# Sheet1.net
KiCad netlist of a schematic drawn in Altium Designer
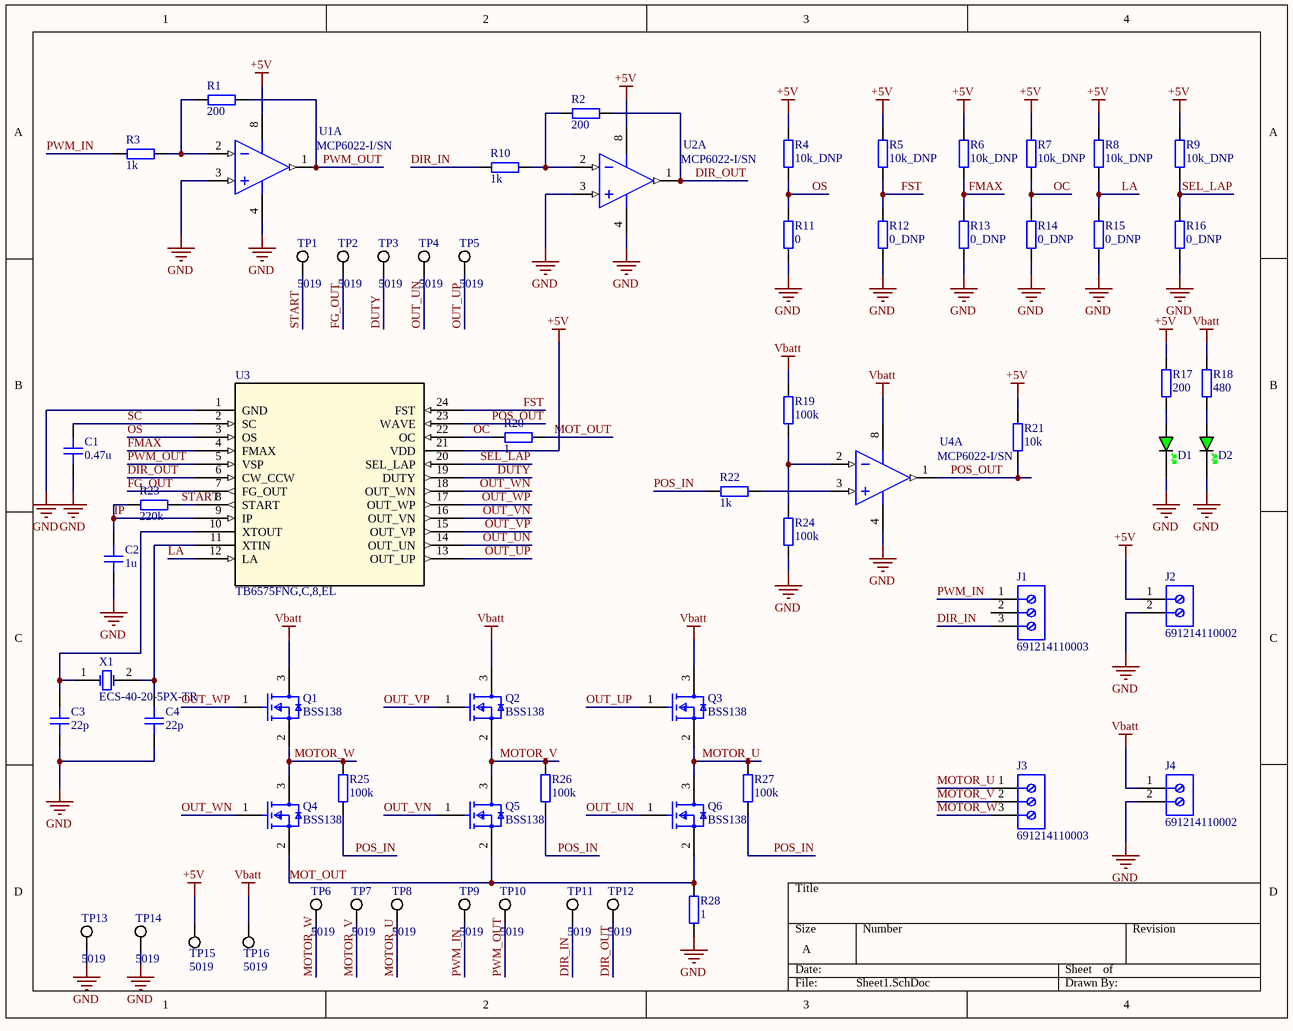
[diagram p0: Sheet1.SchDoc]

(export (version "E")
  (design (tool "Eeschema 10.0.6"))
  (components
    (comp (ref "C1")
      (value "0.47u")
      (footprint "CAP_0805")
      (description "Capacitor SMD 0805")
      (libsource (lib "Schematic-Lib-PhilsLab") (part "CAP_0805"))
    )
    (comp (ref "C2")
      (value "1u")
      (footprint "CAP_0805")
      (description "Capacitor SMD 0805")
      (libsource (lib "Schematic-Lib-PhilsLab") (part "CAP_0805"))
    )
    (comp (ref "C3")
      (value "22p")
      (footprint "CAP_0805")
      (description "Capacitor SMD 0805")
      (libsource (lib "Schematic-Lib-PhilsLab") (part "CAP_0805"))
    )
    (comp (ref "C4")
      (value "22p")
      (footprint "CAP_0805")
      (description "Capacitor SMD 0805")
      (libsource (lib "Schematic-Lib-PhilsLab") (part "CAP_0805"))
    )
    (comp (ref "D1")
      (value "GREEN")
      (footprint "LED_0805_GREEN")
      (description "LED 0805 GREEN SMD")
      (libsource (lib "Schematic-Lib-PhilsLab") (part "LED_0805_GREEN"))
    )
    (comp (ref "D2")
      (value "GREEN")
      (footprint "LED_0805_GREEN")
      (description "LED 0805 GREEN SMD")
      (libsource (lib "Schematic-Lib-PhilsLab") (part "LED_0805_GREEN"))
    )
    (comp (ref "J1")
      (value "691214110003")
      (footprint "691214110003")
      (fields (field (name "VOLTAGE") "300V"))
      (libsource (lib "Altium Content Vault") (part "TBL - 1R - 03P - Screw"))
    )
    (comp (ref "J2")
      (value "691214110002")
      (footprint "691214110002")
      (fields (field (name "VOLTAGE") "300V"))
      (libsource (lib "Altium Content Vault") (part "TBL - 1R - 02P - Screw"))
    )
    (comp (ref "J3")
      (value "691214110003")
      (footprint "691214110003")
      (fields (field (name "VOLTAGE") "300V"))
      (libsource (lib "Altium Content Vault") (part "TBL - 1R - 03P - Screw"))
    )
    (comp (ref "J4")
      (value "691214110002")
      (footprint "691214110002")
      (fields (field (name "VOLTAGE") "300V"))
      (libsource (lib "Altium Content Vault") (part "TBL - 1R - 02P - Screw"))
    )
    (comp (ref "Q1")
      (value "BSS138")
      (footprint "FP-318-08-IPC_B")
      (description "MOSFET N-CH 50V 220MA SOT-23")
      (libsource (lib "Altium Content Vault") (part "3b9c635fedb024a5347a57b145af9cc"))
    )
    (comp (ref "Q2")
      (value "BSS138")
      (footprint "FP-318-08-IPC_B")
      (description "MOSFET N-CH 50V 220MA SOT-23")
      (libsource (lib "Altium Content Vault") (part "3b9c635fedb024a5347a57b145af9cc"))
    )
    (comp (ref "Q3")
      (value "BSS138")
      (footprint "FP-318-08-IPC_B")
      (description "MOSFET N-CH 50V 220MA SOT-23")
      (libsource (lib "Altium Content Vault") (part "3b9c635fedb024a5347a57b145af9cc"))
    )
    (comp (ref "Q4")
      (value "BSS138")
      (footprint "FP-318-08-IPC_B")
      (description "MOSFET N-CH 50V 220MA SOT-23")
      (libsource (lib "Altium Content Vault") (part "3b9c635fedb024a5347a57b145af9cc"))
    )
    (comp (ref "Q5")
      (value "BSS138")
      (footprint "FP-318-08-IPC_B")
      (description "MOSFET N-CH 50V 220MA SOT-23")
      (libsource (lib "Altium Content Vault") (part "3b9c635fedb024a5347a57b145af9cc"))
    )
    (comp (ref "Q6")
      (value "BSS138")
      (footprint "FP-318-08-IPC_B")
      (description "MOSFET N-CH 50V 220MA SOT-23")
      (libsource (lib "Altium Content Vault") (part "3b9c635fedb024a5347a57b145af9cc"))
    )
    (comp (ref "R1")
      (value "200")
      (footprint "RES_0805")
      (description "Resistor SMD 0805")
      (libsource (lib "Schematic-Lib-PhilsLab") (part "RES_0805"))
    )
    (comp (ref "R2")
      (value "200")
      (footprint "RES_0805")
      (description "Resistor SMD 0805")
      (libsource (lib "Schematic-Lib-PhilsLab") (part "RES_0805"))
    )
    (comp (ref "R3")
      (value "1k")
      (footprint "RES_0805")
      (description "Resistor SMD 0805")
      (libsource (lib "Schematic-Lib-PhilsLab") (part "RES_0805"))
    )
    (comp (ref "R4")
      (value "10k_DNP")
      (footprint "RES_0805")
      (description "Resistor SMD 0805")
      (libsource (lib "Schematic-Lib-PhilsLab") (part "RES_0805"))
    )
    (comp (ref "R5")
      (value "10k_DNP")
      (footprint "RES_0805")
      (description "Resistor SMD 0805")
      (libsource (lib "Schematic-Lib-PhilsLab") (part "RES_0805"))
    )
    (comp (ref "R6")
      (value "10k_DNP")
      (footprint "RES_0805")
      (description "Resistor SMD 0805")
      (libsource (lib "Schematic-Lib-PhilsLab") (part "RES_0805"))
    )
    (comp (ref "R7")
      (value "10k_DNP")
      (footprint "RES_0805")
      (description "Resistor SMD 0805")
      (libsource (lib "Schematic-Lib-PhilsLab") (part "RES_0805"))
    )
    (comp (ref "R8")
      (value "10k_DNP")
      (footprint "RES_0805")
      (description "Resistor SMD 0805")
      (libsource (lib "Schematic-Lib-PhilsLab") (part "RES_0805"))
    )
    (comp (ref "R9")
      (value "10k_DNP")
      (footprint "RES_0805")
      (description "Resistor SMD 0805")
      (libsource (lib "Schematic-Lib-PhilsLab") (part "RES_0805"))
    )
    (comp (ref "R10")
      (value "1k")
      (footprint "RES_0805")
      (description "Resistor SMD 0805")
      (libsource (lib "Schematic-Lib-PhilsLab") (part "RES_0805"))
    )
    (comp (ref "R11")
      (value "0")
      (footprint "RES_0805")
      (description "Resistor SMD 0805")
      (libsource (lib "Schematic-Lib-PhilsLab") (part "RES_0805"))
    )
    (comp (ref "R12")
      (value "0_DNP")
      (footprint "RES_0805")
      (description "Resistor SMD 0805")
      (libsource (lib "Schematic-Lib-PhilsLab") (part "RES_0805"))
    )
    (comp (ref "R13")
      (value "0_DNP")
      (footprint "RES_0805")
      (description "Resistor SMD 0805")
      (libsource (lib "Schematic-Lib-PhilsLab") (part "RES_0805"))
    )
    (comp (ref "R14")
      (value "0_DNP")
      (footprint "RES_0805")
      (description "Resistor SMD 0805")
      (libsource (lib "Schematic-Lib-PhilsLab") (part "RES_0805"))
    )
    (comp (ref "R15")
      (value "0_DNP")
      (footprint "RES_0805")
      (description "Resistor SMD 0805")
      (libsource (lib "Schematic-Lib-PhilsLab") (part "RES_0805"))
    )
    (comp (ref "R16")
      (value "0_DNP")
      (footprint "RES_0805")
      (description "Resistor SMD 0805")
      (libsource (lib "Schematic-Lib-PhilsLab") (part "RES_0805"))
    )
    (comp (ref "R17")
      (value "200")
      (footprint "RES_0805")
      (description "Resistor SMD 0805")
      (libsource (lib "Schematic-Lib-PhilsLab") (part "RES_0805"))
    )
    (comp (ref "R18")
      (value "480")
      (footprint "RES_0805")
      (description "Resistor SMD 0805")
      (libsource (lib "Schematic-Lib-PhilsLab") (part "RES_0805"))
    )
    (comp (ref "R19")
      (value "100k")
      (footprint "RES_0805")
      (description "Resistor SMD 0805")
      (libsource (lib "Schematic-Lib-PhilsLab") (part "RES_0805"))
    )
    (comp (ref "R20")
      (value "1")
      (footprint "RES_0805")
      (description "Resistor SMD 0805")
      (libsource (lib "Schematic-Lib-PhilsLab") (part "RES_0805"))
    )
    (comp (ref "R21")
      (value "10k")
      (footprint "RES_0805")
      (description "Resistor SMD 0805")
      (libsource (lib "Schematic-Lib-PhilsLab") (part "RES_0805"))
    )
    (comp (ref "R22")
      (value "1k")
      (footprint "RES_0805")
      (description "Resistor SMD 0805")
      (libsource (lib "Schematic-Lib-PhilsLab") (part "RES_0805"))
    )
    (comp (ref "R23")
      (value "220k")
      (footprint "RES_0805")
      (description "Resistor SMD 0805")
      (libsource (lib "Schematic-Lib-PhilsLab") (part "RES_0805"))
    )
    (comp (ref "R24")
      (value "100k")
      (footprint "RES_0805")
      (description "Resistor SMD 0805")
      (libsource (lib "Schematic-Lib-PhilsLab") (part "RES_0805"))
    )
    (comp (ref "R25")
      (value "100k")
      (footprint "RES_0805")
      (description "Resistor SMD 0805")
      (libsource (lib "Schematic-Lib-PhilsLab") (part "RES_0805"))
    )
    (comp (ref "R26")
      (value "100k")
      (footprint "RES_0805")
      (description "Resistor SMD 0805")
      (libsource (lib "Schematic-Lib-PhilsLab") (part "RES_0805"))
    )
    (comp (ref "R27")
      (value "100k")
      (footprint "RES_0805")
      (description "Resistor SMD 0805")
      (libsource (lib "Schematic-Lib-PhilsLab") (part "RES_0805"))
    )
    (comp (ref "R28")
      (value "1")
      (footprint "RES_0805")
      (description "Resistor SMD 0805")
      (libsource (lib "Schematic-Lib-PhilsLab") (part "RES_0805"))
    )
    (comp (ref "TP1")
      (value "5019")
      (footprint "KSTN-5019_V")
      (description "Test Point, 1 Position SMD, RoHS, Tape and Reel")
      (libsource (lib "Altium Content Vault") (part "TESTPOINT_WHITE"))
    )
    (comp (ref "TP2")
      (value "5019")
      (footprint "KSTN-5019_V")
      (description "Test Point, 1 Position SMD, RoHS, Tape and Reel")
      (libsource (lib "Altium Content Vault") (part "TESTPOINT_WHITE"))
    )
    (comp (ref "TP3")
      (value "5019")
      (footprint "KSTN-5019_V")
      (description "Test Point, 1 Position SMD, RoHS, Tape and Reel")
      (libsource (lib "Altium Content Vault") (part "TESTPOINT_WHITE"))
    )
    (comp (ref "TP4")
      (value "5019")
      (footprint "KSTN-5019_V")
      (description "Test Point, 1 Position SMD, RoHS, Tape and Reel")
      (libsource (lib "Altium Content Vault") (part "TESTPOINT_WHITE"))
    )
    (comp (ref "TP5")
      (value "5019")
      (footprint "KSTN-5019_V")
      (description "Test Point, 1 Position SMD, RoHS, Tape and Reel")
      (libsource (lib "Altium Content Vault") (part "TESTPOINT_WHITE"))
    )
    (comp (ref "TP6")
      (value "5019")
      (footprint "KSTN-5019_V")
      (description "Test Point, 1 Position SMD, RoHS, Tape and Reel")
      (libsource (lib "Altium Content Vault") (part "TESTPOINT_WHITE"))
    )
    (comp (ref "TP7")
      (value "5019")
      (footprint "KSTN-5019_V")
      (description "Test Point, 1 Position SMD, RoHS, Tape and Reel")
      (libsource (lib "Altium Content Vault") (part "TESTPOINT_WHITE"))
    )
    (comp (ref "TP8")
      (value "5019")
      (footprint "KSTN-5019_V")
      (description "Test Point, 1 Position SMD, RoHS, Tape and Reel")
      (libsource (lib "Altium Content Vault") (part "TESTPOINT_WHITE"))
    )
    (comp (ref "TP9")
      (value "5019")
      (footprint "KSTN-5019_V")
      (description "Test Point, 1 Position SMD, RoHS, Tape and Reel")
      (libsource (lib "Altium Content Vault") (part "TESTPOINT_WHITE"))
    )
    (comp (ref "TP10")
      (value "5019")
      (footprint "KSTN-5019_V")
      (description "Test Point, 1 Position SMD, RoHS, Tape and Reel")
      (libsource (lib "Altium Content Vault") (part "TESTPOINT_WHITE"))
    )
    (comp (ref "TP11")
      (value "5019")
      (footprint "KSTN-5019_V")
      (description "Test Point, 1 Position SMD, RoHS, Tape and Reel")
      (libsource (lib "Altium Content Vault") (part "TESTPOINT_WHITE"))
    )
    (comp (ref "TP12")
      (value "5019")
      (footprint "KSTN-5019_V")
      (description "Test Point, 1 Position SMD, RoHS, Tape and Reel")
      (libsource (lib "Altium Content Vault") (part "TESTPOINT_WHITE"))
    )
    (comp (ref "TP13")
      (value "5019")
      (footprint "KSTN-5019_V")
      (description "Test Point, 1 Position SMD, RoHS, Tape and Reel")
      (libsource (lib "Altium Content Vault") (part "TESTPOINT_WHITE"))
    )
    (comp (ref "TP14")
      (value "5019")
      (footprint "KSTN-5019_V")
      (description "Test Point, 1 Position SMD, RoHS, Tape and Reel")
      (libsource (lib "Altium Content Vault") (part "TESTPOINT_WHITE"))
    )
    (comp (ref "TP15")
      (value "5019")
      (footprint "KSTN-5019_V")
      (description "Test Point, 1 Position SMD, RoHS, Tape and Reel")
      (libsource (lib "Altium Content Vault") (part "TESTPOINT_WHITE"))
    )
    (comp (ref "TP16")
      (value "5019")
      (footprint "KSTN-5019_V")
      (description "Test Point, 1 Position SMD, RoHS, Tape and Reel")
      (libsource (lib "Altium Content Vault") (part "TESTPOINT_WHITE"))
    )
    (comp (ref "U1")
      (value "MCP6022-I/SN")
      (footprint "SOIC-SN8_N")
      (description "None")
      (libsource (lib "Altium Content Vault") (part "AMP-OPA-MCP6022-IL8"))
    )
    (comp (ref "U2")
      (value "MCP6022-I/SN")
      (footprint "SOIC-SN8_N")
      (description "None")
      (libsource (lib "Altium Content Vault") (part "AMP-OPA-MCP6022-IL8"))
    )
    (comp (ref "U3")
      (value "TB6575FNG,C,8,EL")
      (footprint "SSOP24-P-300-0p65A_TOS")
      (description "No Description Available")
      (libsource (lib "TB6575FNG,C,8,EL") (part "TB6575FNG,C,8,EL"))
    )
    (comp (ref "U4")
      (value "MCP6022-I/SN")
      (footprint "SOIC-SN8_N")
      (description "None")
      (libsource (lib "Altium Content Vault") (part "AMP-OPA-MCP6022-IL8"))
    )
    (comp (ref "X1")
      (value "ECS-40-20-5PX-TR")
      (footprint "ABRA-ABLS-14.7456MHZ-B2-T_V")
      (description "Low Profile Crystal, 8.0 MHz, +/- 30 ppm, -20 to 70 degC, 2-Pin SMD, RoHS, Tape and Reel")
      (fields (field (name "MANUFACTURER") "ABRACON") (field (name "TOLERANCE") "30PPM"))
      (libsource (lib "Altium Content Vault") (part "XTAL_1-2-2"))
    )
  )
  (nets
    (net (code "1") (name "+5V") (class "Default")
      (node (ref "J2") (pin "1") (pinfunction "1_1") (pintype "passive"))
      (node (ref "R17") (pin "2") (pinfunction "2_2") (pintype "passive"))
      (node (ref "R21") (pin "2") (pinfunction "2_2") (pintype "passive"))
      (node (ref "R4") (pin "2") (pinfunction "2_2") (pintype "passive"))
      (node (ref "R5") (pin "2") (pinfunction "2_2") (pintype "passive"))
      (node (ref "R6") (pin "2") (pinfunction "2_2") (pintype "passive"))
      (node (ref "R7") (pin "2") (pinfunction "2_2") (pintype "passive"))
      (node (ref "R8") (pin "2") (pinfunction "2_2") (pintype "passive"))
      (node (ref "R9") (pin "2") (pinfunction "2_2") (pintype "passive"))
      (node (ref "TP15") (pin "1") (pinfunction "1_1") (pintype "passive"))
      (node (ref "U1") (pin "8") (pinfunction "VDD_8") (pintype "power_in"))
      (node (ref "U2") (pin "8") (pinfunction "VDD_8") (pintype "power_in"))
      (node (ref "U3") (pin "21") (pinfunction "VDD_21") (pintype "power_in"))
    )
    (net (code "2") (name "/DIR_IN") (class "Default")
      (node (ref "J1") (pin "3") (pinfunction "3_3") (pintype "passive"))
      (node (ref "R10") (pin "1") (pinfunction "1_1") (pintype "passive"))
      (node (ref "TP11") (pin "1") (pinfunction "1_1") (pintype "passive"))
    )
    (net (code "3") (name "/DIR_OUT") (class "Default")
      (node (ref "R2") (pin "2") (pinfunction "2_2") (pintype "passive"))
      (node (ref "TP12") (pin "1") (pinfunction "1_1") (pintype "passive"))
      (node (ref "U2") (pin "1") (pinfunction "VOUTA_1") (pintype "output"))
      (node (ref "U3") (pin "6") (pinfunction "CW_CCW_6") (pintype "input"))
    )
    (net (code "4") (name "/DUTY") (class "Default")
      (node (ref "TP3") (pin "1") (pinfunction "1_1") (pintype "passive"))
      (node (ref "U3") (pin "19") (pinfunction "DUTY_19") (pintype "output"))
    )
    (net (code "5") (name "/FG_OUT") (class "Default")
      (node (ref "TP2") (pin "1") (pinfunction "1_1") (pintype "passive"))
      (node (ref "U3") (pin "7") (pinfunction "FG_OUT_7") (pintype "output"))
    )
    (net (code "6") (name "/FMAX") (class "Default")
      (node (ref "R13") (pin "2") (pinfunction "2_2") (pintype "passive"))
      (node (ref "R6") (pin "1") (pinfunction "1_1") (pintype "passive"))
      (node (ref "U3") (pin "4") (pinfunction "FMAX_4") (pintype "input"))
    )
    (net (code "7") (name "/FST") (class "Default")
      (node (ref "R12") (pin "2") (pinfunction "2_2") (pintype "passive"))
      (node (ref "R5") (pin "1") (pinfunction "1_1") (pintype "passive"))
      (node (ref "U3") (pin "24") (pinfunction "FST_24") (pintype "input"))
    )
    (net (code "8") (name "/IP") (class "Default")
      (node (ref "C2") (pin "2") (pinfunction "2_2") (pintype "passive"))
      (node (ref "R23") (pin "2") (pinfunction "2_2") (pintype "passive"))
      (node (ref "U3") (pin "9") (pinfunction "IP_9") (pintype "input"))
    )
    (net (code "9") (name "/LA") (class "Default")
      (node (ref "R15") (pin "2") (pinfunction "2_2") (pintype "passive"))
      (node (ref "R8") (pin "1") (pinfunction "1_1") (pintype "passive"))
      (node (ref "U3") (pin "12") (pinfunction "LA_12") (pintype "input"))
    )
    (net (code "10") (name "/MOTOR_U") (class "Default")
      (node (ref "J3") (pin "1") (pinfunction "1_1") (pintype "passive"))
      (node (ref "Q3") (pin "2") (pinfunction "S_2") (pintype "passive"))
      (node (ref "Q6") (pin "3") (pinfunction "D_3") (pintype "passive"))
      (node (ref "R27") (pin "2") (pinfunction "2_2") (pintype "passive"))
      (node (ref "TP8") (pin "1") (pinfunction "1_1") (pintype "passive"))
    )
    (net (code "11") (name "/MOTOR_V") (class "Default")
      (node (ref "J3") (pin "2") (pinfunction "2_2") (pintype "passive"))
      (node (ref "Q2") (pin "2") (pinfunction "S_2") (pintype "passive"))
      (node (ref "Q5") (pin "3") (pinfunction "D_3") (pintype "passive"))
      (node (ref "R26") (pin "2") (pinfunction "2_2") (pintype "passive"))
      (node (ref "TP7") (pin "1") (pinfunction "1_1") (pintype "passive"))
    )
    (net (code "12") (name "/MOTOR_W") (class "Default")
      (node (ref "J3") (pin "3") (pinfunction "3_3") (pintype "passive"))
      (node (ref "Q1") (pin "2") (pinfunction "S_2") (pintype "passive"))
      (node (ref "Q4") (pin "3") (pinfunction "D_3") (pintype "passive"))
      (node (ref "R25") (pin "2") (pinfunction "2_2") (pintype "passive"))
      (node (ref "TP6") (pin "1") (pinfunction "1_1") (pintype "passive"))
    )
    (net (code "13") (name "/MOT_OUT") (class "Default")
      (node (ref "Q4") (pin "2") (pinfunction "S_2") (pintype "passive"))
      (node (ref "Q5") (pin "2") (pinfunction "S_2") (pintype "passive"))
      (node (ref "Q6") (pin "2") (pinfunction "S_2") (pintype "passive"))
      (node (ref "R20") (pin "1") (pinfunction "1_1") (pintype "passive"))
      (node (ref "R28") (pin "2") (pinfunction "2_2") (pintype "passive"))
    )
    (net (code "14") (name "/OC") (class "Default")
      (node (ref "R14") (pin "2") (pinfunction "2_2") (pintype "passive"))
      (node (ref "R20") (pin "2") (pinfunction "2_2") (pintype "passive"))
      (node (ref "R7") (pin "1") (pinfunction "1_1") (pintype "passive"))
      (node (ref "U3") (pin "22") (pinfunction "OC_22") (pintype "input"))
    )
    (net (code "15") (name "/OS") (class "Default")
      (node (ref "R11") (pin "2") (pinfunction "2_2") (pintype "passive"))
      (node (ref "R4") (pin "1") (pinfunction "1_1") (pintype "passive"))
      (node (ref "U3") (pin "3") (pinfunction "OS_3") (pintype "input"))
    )
    (net (code "16") (name "/OUT_UN") (class "Default")
      (node (ref "Q6") (pin "1") (pinfunction "G_1") (pintype "passive"))
      (node (ref "TP4") (pin "1") (pinfunction "1_1") (pintype "passive"))
      (node (ref "U3") (pin "14") (pinfunction "OUT_UN_14") (pintype "output"))
    )
    (net (code "17") (name "/OUT_UP") (class "Default")
      (node (ref "Q3") (pin "1") (pinfunction "G_1") (pintype "passive"))
      (node (ref "TP5") (pin "1") (pinfunction "1_1") (pintype "passive"))
      (node (ref "U3") (pin "13") (pinfunction "OUT_UP_13") (pintype "output"))
    )
    (net (code "18") (name "/OUT_VN") (class "Default")
      (node (ref "Q5") (pin "1") (pinfunction "G_1") (pintype "passive"))
      (node (ref "U3") (pin "16") (pinfunction "OUT_VN_16") (pintype "output"))
    )
    (net (code "19") (name "/OUT_VP") (class "Default")
      (node (ref "Q2") (pin "1") (pinfunction "G_1") (pintype "passive"))
      (node (ref "U3") (pin "15") (pinfunction "OUT_VP_15") (pintype "output"))
    )
    (net (code "20") (name "/OUT_WN") (class "Default")
      (node (ref "Q4") (pin "1") (pinfunction "G_1") (pintype "passive"))
      (node (ref "U3") (pin "18") (pinfunction "OUT_WN_18") (pintype "output"))
    )
    (net (code "21") (name "/OUT_WP") (class "Default")
      (node (ref "Q1") (pin "1") (pinfunction "G_1") (pintype "passive"))
      (node (ref "U3") (pin "17") (pinfunction "OUT_WP_17") (pintype "output"))
    )
    (net (code "22") (name "/POS_IN") (class "Default")
      (node (ref "R22") (pin "1") (pinfunction "1_1") (pintype "passive"))
      (node (ref "R25") (pin "1") (pinfunction "1_1") (pintype "passive"))
      (node (ref "R26") (pin "1") (pinfunction "1_1") (pintype "passive"))
      (node (ref "R27") (pin "1") (pinfunction "1_1") (pintype "passive"))
    )
    (net (code "23") (name "/POS_OUT") (class "Default")
      (node (ref "R21") (pin "1") (pinfunction "1_1") (pintype "passive"))
      (node (ref "U3") (pin "23") (pinfunction "WAVE_23") (pintype "input"))
      (node (ref "U4") (pin "1") (pinfunction "VOUTA_1") (pintype "output"))
    )
    (net (code "24") (name "/PWM_IN") (class "Default")
      (node (ref "J1") (pin "1") (pinfunction "1_1") (pintype "passive"))
      (node (ref "R3") (pin "1") (pinfunction "1_1") (pintype "passive"))
      (node (ref "TP9") (pin "1") (pinfunction "1_1") (pintype "passive"))
    )
    (net (code "25") (name "/PWM_OUT") (class "Default")
      (node (ref "R1") (pin "2") (pinfunction "2_2") (pintype "passive"))
      (node (ref "TP10") (pin "1") (pinfunction "1_1") (pintype "passive"))
      (node (ref "U1") (pin "1") (pinfunction "VOUTA_1") (pintype "output"))
      (node (ref "U3") (pin "5") (pinfunction "VSP_5") (pintype "input"))
    )
    (net (code "26") (name "/SC") (class "Default")
      (node (ref "C1") (pin "2") (pinfunction "2_2") (pintype "passive"))
      (node (ref "U3") (pin "2") (pinfunction "SC_2") (pintype "input"))
    )
    (net (code "27") (name "/SEL_LAP") (class "Default")
      (node (ref "R16") (pin "2") (pinfunction "2_2") (pintype "passive"))
      (node (ref "R9") (pin "1") (pinfunction "1_1") (pintype "passive"))
      (node (ref "U3") (pin "20") (pinfunction "SEL_LAP_20") (pintype "input"))
    )
    (net (code "28") (name "/START") (class "Default")
      (node (ref "R23") (pin "1") (pinfunction "1_1") (pintype "passive"))
      (node (ref "TP1") (pin "1") (pinfunction "1_1") (pintype "passive"))
      (node (ref "U3") (pin "8") (pinfunction "START_8") (pintype "output"))
    )
    (net (code "29") (name "GND") (class "Default")
      (node (ref "C1") (pin "1") (pinfunction "1_1") (pintype "passive"))
      (node (ref "C2") (pin "1") (pinfunction "1_1") (pintype "passive"))
      (node (ref "C3") (pin "1") (pinfunction "1_1") (pintype "passive"))
      (node (ref "C4") (pin "1") (pinfunction "1_1") (pintype "passive"))
      (node (ref "D1") (pin "K") (pinfunction "K_K") (pintype "passive"))
      (node (ref "D2") (pin "K") (pinfunction "K_K") (pintype "passive"))
      (node (ref "J2") (pin "2") (pinfunction "2_2") (pintype "passive"))
      (node (ref "J4") (pin "2") (pinfunction "2_2") (pintype "passive"))
      (node (ref "R11") (pin "1") (pinfunction "1_1") (pintype "passive"))
      (node (ref "R12") (pin "1") (pinfunction "1_1") (pintype "passive"))
      (node (ref "R13") (pin "1") (pinfunction "1_1") (pintype "passive"))
      (node (ref "R14") (pin "1") (pinfunction "1_1") (pintype "passive"))
      (node (ref "R15") (pin "1") (pinfunction "1_1") (pintype "passive"))
      (node (ref "R16") (pin "1") (pinfunction "1_1") (pintype "passive"))
      (node (ref "R24") (pin "1") (pinfunction "1_1") (pintype "passive"))
      (node (ref "R28") (pin "1") (pinfunction "1_1") (pintype "passive"))
      (node (ref "TP13") (pin "1") (pinfunction "1_1") (pintype "passive"))
      (node (ref "TP14") (pin "1") (pinfunction "1_1") (pintype "passive"))
      (node (ref "U1") (pin "3") (pinfunction "VINA+_3") (pintype "input"))
      (node (ref "U1") (pin "4") (pinfunction "VSS_4") (pintype "power_in"))
      (node (ref "U2") (pin "3") (pinfunction "VINA+_3") (pintype "input"))
      (node (ref "U2") (pin "4") (pinfunction "VSS_4") (pintype "power_in"))
      (node (ref "U3") (pin "1") (pinfunction "GND_1") (pintype "power_in"))
      (node (ref "U4") (pin "4") (pinfunction "VSS_4") (pintype "power_in"))
    )
    (net (code "30") (name "Net-(D1-PadA)") (class "Default")
      (node (ref "D1") (pin "A") (pinfunction "A_A") (pintype "passive"))
      (node (ref "R17") (pin "1") (pinfunction "1_1") (pintype "passive"))
    )
    (net (code "31") (name "Net-(D2-PadA)") (class "Default")
      (node (ref "D2") (pin "A") (pinfunction "A_A") (pintype "passive"))
      (node (ref "R18") (pin "1") (pinfunction "1_1") (pintype "passive"))
    )
    (net (code "32") (name "Net-(U1A-VINA-)") (class "Default")
      (node (ref "R1") (pin "1") (pinfunction "1_1") (pintype "passive"))
      (node (ref "R3") (pin "2") (pinfunction "2_2") (pintype "passive"))
      (node (ref "U1") (pin "2") (pinfunction "VINA-_2") (pintype "input"))
    )
    (net (code "33") (name "Net-(U2A-VINA-)") (class "Default")
      (node (ref "R10") (pin "2") (pinfunction "2_2") (pintype "passive"))
      (node (ref "R2") (pin "1") (pinfunction "1_1") (pintype "passive"))
      (node (ref "U2") (pin "2") (pinfunction "VINA-_2") (pintype "input"))
    )
    (net (code "34") (name "Net-(U3-XTIN)") (class "Default")
      (node (ref "C4") (pin "2") (pinfunction "2_2") (pintype "passive"))
      (node (ref "U3") (pin "11") (pinfunction "XTIN_11") (pintype "passive"))
      (node (ref "X1") (pin "2") (pinfunction "X2_2") (pintype "passive"))
    )
    (net (code "35") (name "Net-(U3-XTOUT)") (class "Default")
      (node (ref "C3") (pin "2") (pinfunction "2_2") (pintype "passive"))
      (node (ref "U3") (pin "10") (pinfunction "XTOUT_10") (pintype "passive"))
      (node (ref "X1") (pin "1") (pinfunction "X1_1") (pintype "passive"))
    )
    (net (code "36") (name "Net-(U4A-VINA+)") (class "Default")
      (node (ref "R22") (pin "2") (pinfunction "2_2") (pintype "passive"))
      (node (ref "U4") (pin "3") (pinfunction "VINA+_3") (pintype "input"))
    )
    (net (code "37") (name "Net-(U4A-VINA-)") (class "Default")
      (node (ref "R19") (pin "1") (pinfunction "1_1") (pintype "passive"))
      (node (ref "R24") (pin "2") (pinfunction "2_2") (pintype "passive"))
      (node (ref "U4") (pin "2") (pinfunction "VINA-_2") (pintype "input"))
    )
    (net (code "38") (name "Vbatt") (class "Default")
      (node (ref "J4") (pin "1") (pinfunction "1_1") (pintype "passive"))
      (node (ref "Q1") (pin "3") (pinfunction "D_3") (pintype "passive"))
      (node (ref "Q2") (pin "3") (pinfunction "D_3") (pintype "passive"))
      (node (ref "Q3") (pin "3") (pinfunction "D_3") (pintype "passive"))
      (node (ref "R18") (pin "2") (pinfunction "2_2") (pintype "passive"))
      (node (ref "R19") (pin "2") (pinfunction "2_2") (pintype "passive"))
      (node (ref "TP16") (pin "1") (pinfunction "1_1") (pintype "passive"))
      (node (ref "U4") (pin "8") (pinfunction "VDD_8") (pintype "power_in"))
    )
    (net (code "39") (name "unconnected-(J1-Pad2)") (class "Default")
      (node (ref "J1") (pin "2") (pinfunction "2_2") (pintype "passive"))
    )
  )
)
